# PatGen.net
KiCad netlist of a schematic drawn in EAGLE
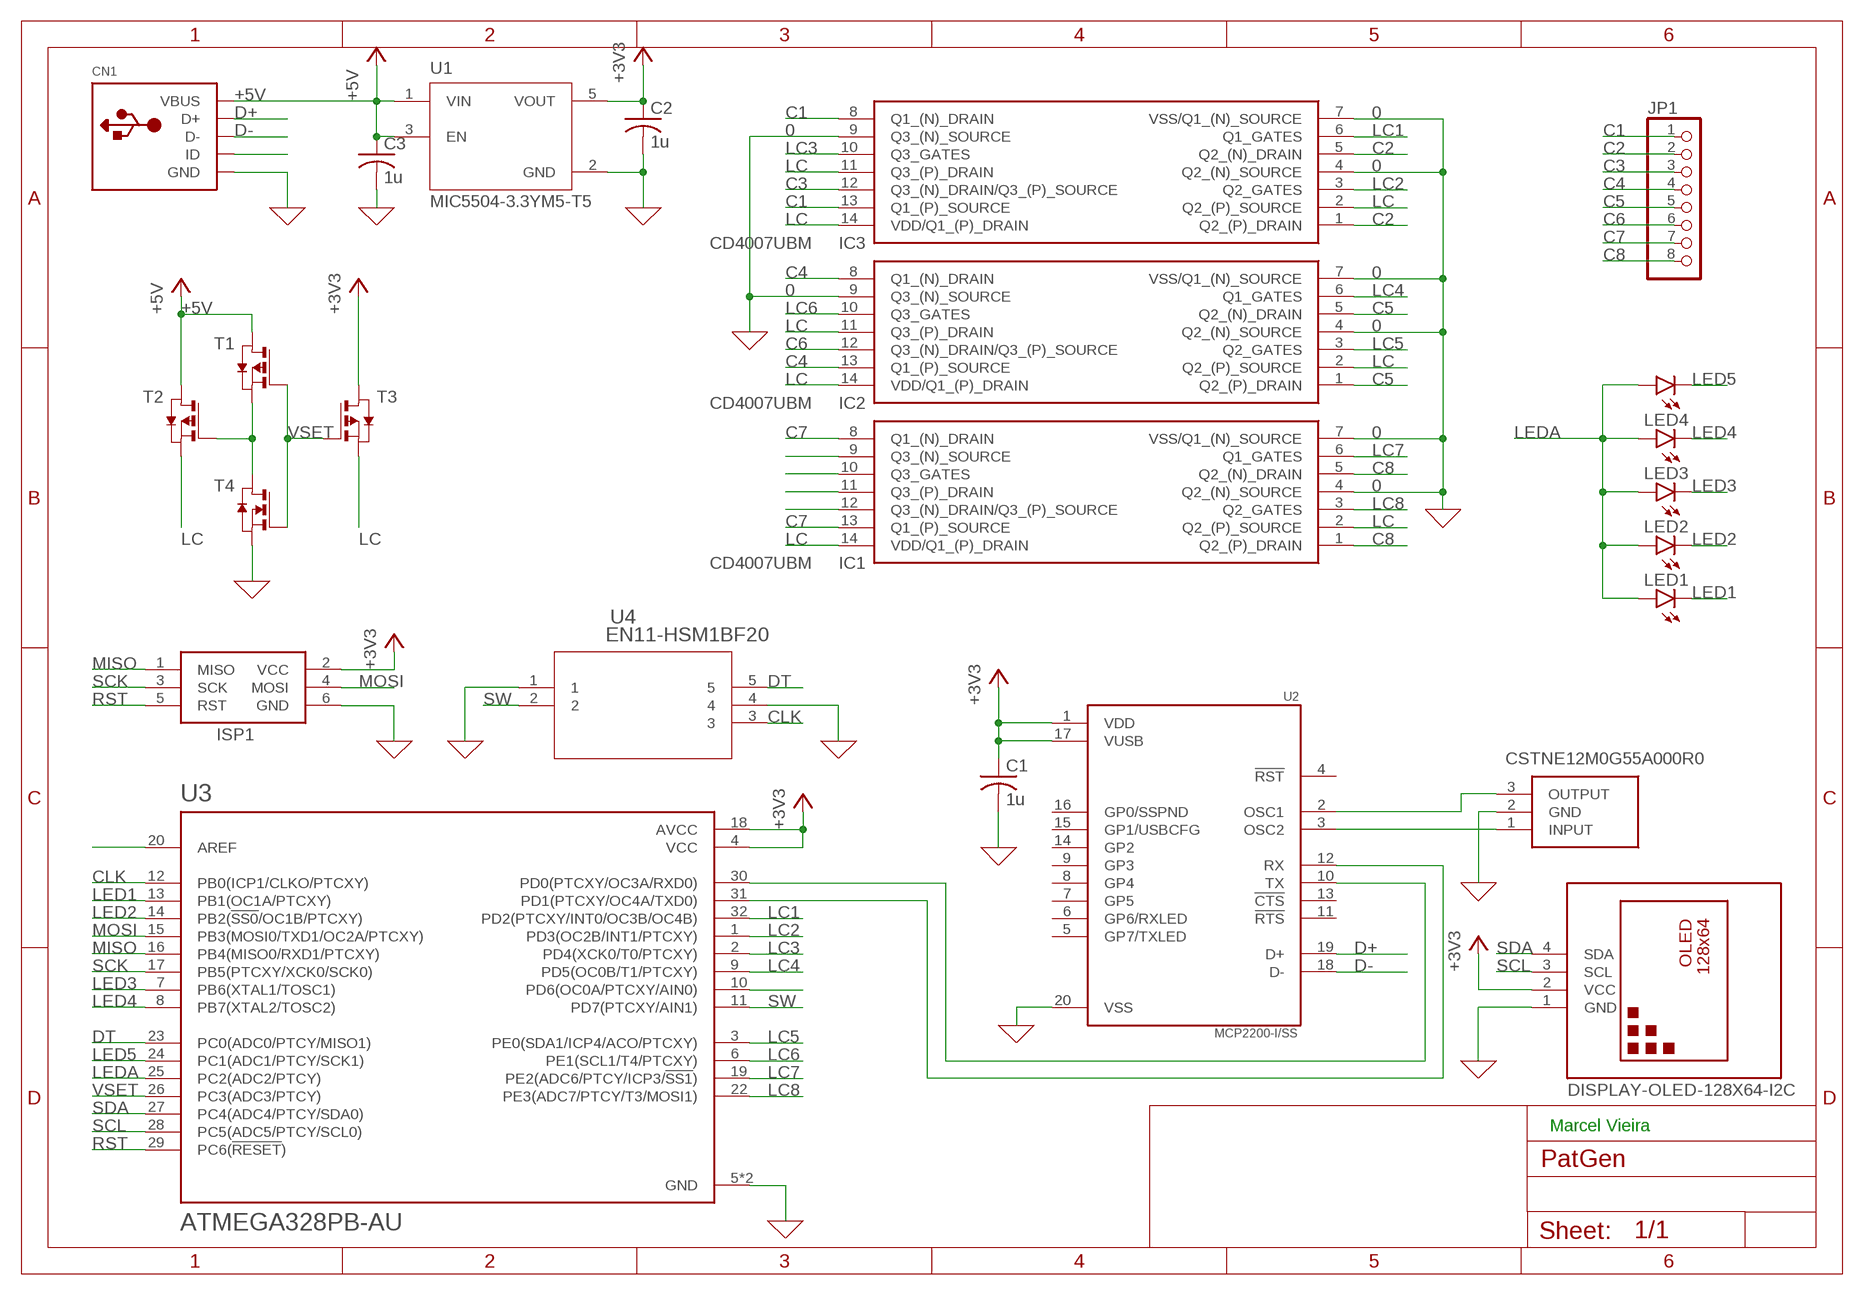
[diagram p0: schematic, sheet 1]

(export (version "E")
  (design (tool "Eeschema 10.0.6"))
  (components
    (comp (ref "C1")
      (value "1u")
      (footprint "eagle-import:C0805")
      (libsource (lib "eagle-import") (part "C-USC0805"))
    )
    (comp (ref "C2")
      (value "1u")
      (footprint "eagle-import:C0805")
      (libsource (lib "eagle-import") (part "C-USC0805"))
    )
    (comp (ref "C3")
      (value "1u")
      (footprint "eagle-import:C0805")
      (libsource (lib "eagle-import") (part "C-USC0805"))
    )
    (comp (ref "CN1")
      (value "USBMINIB")
      (footprint "eagle-import:USB-MINIB")
      (libsource (lib "eagle-import") (part "USBMINIB"))
    )
    (comp (ref "IC1")
      (value "CD4007UBM")
      (footprint "eagle-import:SOIC127P600X175-14N")
      (fields (field (name "MOUSER_PART_NUMBER") "595-CD4007UBM"))
      (libsource (lib "eagle-import") (part "CD4007UBM"))
    )
    (comp (ref "IC2")
      (value "CD4007UBM")
      (footprint "eagle-import:SOIC127P600X175-14N")
      (fields (field (name "MOUSER_PART_NUMBER") "595-CD4007UBM"))
      (libsource (lib "eagle-import") (part "CD4007UBM"))
    )
    (comp (ref "IC3")
      (value "CD4007UBM")
      (footprint "eagle-import:SOIC127P600X175-14N")
      (fields (field (name "MOUSER_PART_NUMBER") "595-CD4007UBM"))
      (libsource (lib "eagle-import") (part "CD4007UBM"))
    )
    (comp (ref "ISP1")
      (value "AVRISP-6")
      (footprint "eagle-import:AVRISP")
      (libsource (lib "eagle-import") (part "AVRISP-6"))
    )
    (comp (ref "JP1")
      (value "PINHD-1X8-3.5MM")
      (footprint "eagle-import:1X08-3.5MM")
      (libsource (lib "eagle-import") (part "PINHD-1X8-3.5MM"))
    )
    (comp (ref "LED1")
      (value "LEDCHIP-LED0805")
      (footprint "eagle-import:CHIP-LED0805")
      (libsource (lib "eagle-import") (part "LEDCHIP-LED0805"))
    )
    (comp (ref "LED2")
      (value "LEDCHIP-LED0805")
      (footprint "eagle-import:CHIP-LED0805")
      (libsource (lib "eagle-import") (part "LEDCHIP-LED0805"))
    )
    (comp (ref "LED3")
      (value "LEDCHIP-LED0805")
      (footprint "eagle-import:CHIP-LED0805")
      (libsource (lib "eagle-import") (part "LEDCHIP-LED0805"))
    )
    (comp (ref "LED4")
      (value "LEDCHIP-LED0805")
      (footprint "eagle-import:CHIP-LED0805")
      (libsource (lib "eagle-import") (part "LEDCHIP-LED0805"))
    )
    (comp (ref "LED5")
      (value "LEDCHIP-LED0805")
      (footprint "eagle-import:CHIP-LED0805")
      (libsource (lib "eagle-import") (part "LEDCHIP-LED0805"))
    )
    (comp (ref "T1")
      (value "PMOSSOT23")
      (footprint "eagle-import:SOT-23")
      (libsource (lib "eagle-import") (part "PMOSSOT23"))
    )
    (comp (ref "T2")
      (value "PMOSSOT23")
      (footprint "eagle-import:SOT-23")
      (libsource (lib "eagle-import") (part "PMOSSOT23"))
    )
    (comp (ref "T3")
      (value "PMOSSOT23")
      (footprint "eagle-import:SOT-23")
      (libsource (lib "eagle-import") (part "PMOSSOT23"))
    )
    (comp (ref "T4")
      (value "NMOSSOT23")
      (footprint "eagle-import:SOT-23")
      (libsource (lib "eagle-import") (part "NMOSSOT23"))
    )
    (comp (ref "U$1")
      (value "DISPLAY-OLED-128X64-I2C")
      (footprint "eagle-import:DISPLAY-OLED-128X64-I2C")
      (libsource (lib "eagle-import") (part "DISPLAY-OLED-128X64-I2C"))
    )
    (comp (ref "U1")
      (value "MIC5504-3.3YM5-T5")
      (footprint "eagle-import:SOT95P280X145-5N")
      (fields (field (name "MF") "Microchip"))
      (libsource (lib "eagle-import") (part "MIC5504-3.3YM5-T5"))
    )
    (comp (ref "U2")
      (value "MCP2200-I/SS")
      (footprint "eagle-import:SOP65P780X200-20N")
      (fields (field (name "MF") "Microchip"))
      (libsource (lib "eagle-import") (part "MCP2200-I/SS"))
    )
    (comp (ref "U3")
      (value "ATMEGA328PB-AU")
      (footprint "eagle-import:QFP80P900X900X120-32N")
      (fields (field (name "MF") "Microchip Technology / Atmel"))
      (libsource (lib "eagle-import") (part "ATMEGA328PB-AU"))
    )
    (comp (ref "U4")
      (value "EN11-HSM1BF20")
      (footprint "eagle-import:EN11-HSM_TTE")
      (libsource (lib "eagle-import") (part "EN11-HSM1BF20"))
    )
    (comp (ref "Y1")
      (value "CSTNE12M0G55A000R0")
      (footprint "eagle-import:CSTNE12M0G55A000R0")
      (fields (field (name "MOUSER_PART_NUMBER") "81-CSTNE12M0G55A000R"))
      (libsource (lib "eagle-import") (part "CSTNE12M0G55A000R0"))
    )
  )
  (nets
    (net (code "1") (name "+3V3") (class "Default")
      (node (ref "C1") (pin "1") (pinfunction "1_1") (pintype "passive"))
      (node (ref "C2") (pin "1") (pinfunction "1_1") (pintype "passive"))
      (node (ref "ISP1") (pin "2") (pinfunction "VCC_2") (pintype "power_in"))
      (node (ref "T3") (pin "1") (pinfunction "D_1") (pintype "passive"))
      (node (ref "U$1") (pin "2") (pinfunction "VCC_2") (pintype "power_in"))
      (node (ref "U1") (pin "5") (pinfunction "VOUT_5") (pintype "output"))
      (node (ref "U2") (pin "1") (pinfunction "VDD_1") (pintype "power_in"))
      (node (ref "U2") (pin "17") (pinfunction "VUSB_17") (pintype "power_in"))
      (node (ref "U3") (pin "18") (pinfunction "AVCC_18") (pintype "power_in"))
      (node (ref "U3") (pin "4") (pinfunction "VCC_4") (pintype "power_in"))
    )
    (net (code "2") (name "+5V") (class "Default")
      (node (ref "C3") (pin "1") (pinfunction "1_1") (pintype "passive"))
      (node (ref "CN1") (pin "VBUS") (pinfunction "VBUS_VBUS") (pintype "power_in"))
      (node (ref "T1") (pin "1") (pinfunction "D_1") (pintype "passive"))
      (node (ref "T2") (pin "1") (pinfunction "D_1") (pintype "passive"))
      (node (ref "U1") (pin "1") (pinfunction "VIN_1") (pintype "input"))
      (node (ref "U1") (pin "3") (pinfunction "EN_3") (pintype "input"))
    )
    (net (code "3") (name "/C1") (class "Default")
      (node (ref "IC3") (pin "13") (pinfunction "Q1_(P)_SOURCE_13") (pintype "bidirectional"))
      (node (ref "IC3") (pin "8") (pinfunction "Q1_(N)_DRAIN_8") (pintype "bidirectional"))
      (node (ref "JP1") (pin "1") (pinfunction "1_1") (pintype "passive"))
    )
    (net (code "4") (name "/C2") (class "Default")
      (node (ref "IC3") (pin "1") (pinfunction "Q2_(P)_DRAIN_1") (pintype "bidirectional"))
      (node (ref "IC3") (pin "5") (pinfunction "Q2_(N)_DRAIN_5") (pintype "bidirectional"))
      (node (ref "JP1") (pin "2") (pinfunction "2_2") (pintype "passive"))
    )
    (net (code "5") (name "/C3") (class "Default")
      (node (ref "IC3") (pin "12") (pinfunction "Q3_(N)_DRAIN/Q3_(P)_SOURCE_12") (pintype "bidirectional"))
      (node (ref "JP1") (pin "3") (pinfunction "3_3") (pintype "passive"))
    )
    (net (code "6") (name "/C4") (class "Default")
      (node (ref "IC2") (pin "13") (pinfunction "Q1_(P)_SOURCE_13") (pintype "bidirectional"))
      (node (ref "IC2") (pin "8") (pinfunction "Q1_(N)_DRAIN_8") (pintype "bidirectional"))
      (node (ref "JP1") (pin "4") (pinfunction "4_4") (pintype "passive"))
    )
    (net (code "7") (name "/C5") (class "Default")
      (node (ref "IC2") (pin "1") (pinfunction "Q2_(P)_DRAIN_1") (pintype "bidirectional"))
      (node (ref "IC2") (pin "5") (pinfunction "Q2_(N)_DRAIN_5") (pintype "bidirectional"))
      (node (ref "JP1") (pin "5") (pinfunction "5_5") (pintype "passive"))
    )
    (net (code "8") (name "/C6") (class "Default")
      (node (ref "IC2") (pin "12") (pinfunction "Q3_(N)_DRAIN/Q3_(P)_SOURCE_12") (pintype "bidirectional"))
      (node (ref "JP1") (pin "6") (pinfunction "6_6") (pintype "passive"))
    )
    (net (code "9") (name "/C7") (class "Default")
      (node (ref "IC1") (pin "13") (pinfunction "Q1_(P)_SOURCE_13") (pintype "bidirectional"))
      (node (ref "IC1") (pin "8") (pinfunction "Q1_(N)_DRAIN_8") (pintype "bidirectional"))
      (node (ref "JP1") (pin "7") (pinfunction "7_7") (pintype "passive"))
    )
    (net (code "10") (name "/C8") (class "Default")
      (node (ref "IC1") (pin "1") (pinfunction "Q2_(P)_DRAIN_1") (pintype "bidirectional"))
      (node (ref "IC1") (pin "5") (pinfunction "Q2_(N)_DRAIN_5") (pintype "bidirectional"))
      (node (ref "JP1") (pin "8") (pinfunction "8_8") (pintype "passive"))
    )
    (net (code "11") (name "/CLK") (class "Default")
      (node (ref "U3") (pin "12") (pinfunction "PB0(ICP1/CLKO/PTCXY)_12") (pintype "bidirectional"))
      (node (ref "U4") (pin "3") (pinfunction "3_3") (pintype "passive"))
    )
    (net (code "12") (name "/D+") (class "Default")
      (node (ref "CN1") (pin "D+") (pinfunction "D+_D+") (pintype "bidirectional"))
      (node (ref "U2") (pin "19") (pinfunction "D+_19") (pintype "bidirectional"))
    )
    (net (code "13") (name "/D-") (class "Default")
      (node (ref "CN1") (pin "D-") (pinfunction "D-_D-") (pintype "bidirectional"))
      (node (ref "U2") (pin "18") (pinfunction "D-_18") (pintype "bidirectional"))
    )
    (net (code "14") (name "/DT") (class "Default")
      (node (ref "U3") (pin "23") (pinfunction "PC0(ADC0/PTCY/MISO1)_23") (pintype "bidirectional"))
      (node (ref "U4") (pin "5") (pinfunction "5_5") (pintype "passive"))
    )
    (net (code "15") (name "/LC") (class "Default")
      (node (ref "IC1") (pin "14") (pinfunction "VDD/Q1_(P)_DRAIN_14") (pintype "bidirectional"))
      (node (ref "IC1") (pin "2") (pinfunction "Q2_(P)_SOURCE_2") (pintype "bidirectional"))
      (node (ref "IC2") (pin "11") (pinfunction "Q3_(P)_DRAIN_11") (pintype "bidirectional"))
      (node (ref "IC2") (pin "14") (pinfunction "VDD/Q1_(P)_DRAIN_14") (pintype "bidirectional"))
      (node (ref "IC2") (pin "2") (pinfunction "Q2_(P)_SOURCE_2") (pintype "bidirectional"))
      (node (ref "IC3") (pin "11") (pinfunction "Q3_(P)_DRAIN_11") (pintype "bidirectional"))
      (node (ref "IC3") (pin "14") (pinfunction "VDD/Q1_(P)_DRAIN_14") (pintype "bidirectional"))
      (node (ref "IC3") (pin "2") (pinfunction "Q2_(P)_SOURCE_2") (pintype "bidirectional"))
      (node (ref "T2") (pin "2") (pinfunction "S_2") (pintype "passive"))
      (node (ref "T3") (pin "2") (pinfunction "S_2") (pintype "passive"))
    )
    (net (code "16") (name "/LC1") (class "Default")
      (node (ref "IC3") (pin "6") (pinfunction "Q1_GATES_6") (pintype "bidirectional"))
      (node (ref "U3") (pin "32") (pinfunction "PD2(PTCXY/INT0/OC3B/OC4B)_32") (pintype "bidirectional"))
    )
    (net (code "17") (name "/LC2") (class "Default")
      (node (ref "IC3") (pin "3") (pinfunction "Q2_GATES_3") (pintype "bidirectional"))
      (node (ref "U3") (pin "1") (pinfunction "PD3(OC2B/INT1/PTCXY)_1") (pintype "bidirectional"))
    )
    (net (code "18") (name "/LC3") (class "Default")
      (node (ref "IC3") (pin "10") (pinfunction "Q3_GATES_10") (pintype "bidirectional"))
      (node (ref "U3") (pin "2") (pinfunction "PD4(XCK0/T0/PTCXY)_2") (pintype "bidirectional"))
    )
    (net (code "19") (name "/LC4") (class "Default")
      (node (ref "IC2") (pin "6") (pinfunction "Q1_GATES_6") (pintype "bidirectional"))
      (node (ref "U3") (pin "9") (pinfunction "PD5(OC0B/T1/PTCXY)_9") (pintype "bidirectional"))
    )
    (net (code "20") (name "/LC5") (class "Default")
      (node (ref "IC2") (pin "3") (pinfunction "Q2_GATES_3") (pintype "bidirectional"))
      (node (ref "U3") (pin "3") (pinfunction "PE0(SDA1/ICP4/ACO/PTCXY)_3") (pintype "bidirectional"))
    )
    (net (code "21") (name "/LC6") (class "Default")
      (node (ref "IC2") (pin "10") (pinfunction "Q3_GATES_10") (pintype "bidirectional"))
      (node (ref "U3") (pin "6") (pinfunction "PE1(SCL1/T4/PTCXY)_6") (pintype "bidirectional"))
    )
    (net (code "22") (name "/LC7") (class "Default")
      (node (ref "IC1") (pin "6") (pinfunction "Q1_GATES_6") (pintype "bidirectional"))
      (node (ref "U3") (pin "19") (pinfunction "PE2(ADC6/PTCY/ICP3/~{SS1})_19") (pintype "bidirectional"))
    )
    (net (code "23") (name "/LC8") (class "Default")
      (node (ref "IC1") (pin "3") (pinfunction "Q2_GATES_3") (pintype "bidirectional"))
      (node (ref "U3") (pin "22") (pinfunction "PE3(ADC7/PTCY/T3/MOSI1)_22") (pintype "bidirectional"))
    )
    (net (code "24") (name "/LED1") (class "Default")
      (node (ref "LED1") (pin "C") (pinfunction "C_C") (pintype "passive"))
      (node (ref "U3") (pin "13") (pinfunction "PB1(OC1A/PTCXY)_13") (pintype "bidirectional"))
    )
    (net (code "25") (name "/LED2") (class "Default")
      (node (ref "LED2") (pin "C") (pinfunction "C_C") (pintype "passive"))
      (node (ref "U3") (pin "14") (pinfunction "PB2(~{SS0}/OC1B/PTCXY)_14") (pintype "bidirectional"))
    )
    (net (code "26") (name "/LED3") (class "Default")
      (node (ref "LED3") (pin "C") (pinfunction "C_C") (pintype "passive"))
      (node (ref "U3") (pin "7") (pinfunction "PB6(XTAL1/TOSC1)_7") (pintype "bidirectional"))
    )
    (net (code "27") (name "/LED4") (class "Default")
      (node (ref "LED4") (pin "C") (pinfunction "C_C") (pintype "passive"))
      (node (ref "U3") (pin "8") (pinfunction "PB7(XTAL2/TOSC2)_8") (pintype "bidirectional"))
    )
    (net (code "28") (name "/LED5") (class "Default")
      (node (ref "LED5") (pin "C") (pinfunction "C_C") (pintype "passive"))
      (node (ref "U3") (pin "24") (pinfunction "PC1(ADC1/PTCY/SCK1)_24") (pintype "bidirectional"))
    )
    (net (code "29") (name "/LEDA") (class "Default")
      (node (ref "LED1") (pin "A") (pinfunction "A_A") (pintype "passive"))
      (node (ref "LED2") (pin "A") (pinfunction "A_A") (pintype "passive"))
      (node (ref "LED3") (pin "A") (pinfunction "A_A") (pintype "passive"))
      (node (ref "LED4") (pin "A") (pinfunction "A_A") (pintype "passive"))
      (node (ref "LED5") (pin "A") (pinfunction "A_A") (pintype "passive"))
      (node (ref "U3") (pin "25") (pinfunction "PC2(ADC2/PTCY)_25") (pintype "bidirectional"))
    )
    (net (code "30") (name "/MISO") (class "Default")
      (node (ref "ISP1") (pin "1") (pinfunction "MISO_1") (pintype "input"))
      (node (ref "U3") (pin "16") (pinfunction "PB4(MISO0/RXD1/PTCXY)_16") (pintype "bidirectional"))
    )
    (net (code "31") (name "/MOSI") (class "Default")
      (node (ref "ISP1") (pin "4") (pinfunction "MOSI_4") (pintype "output"))
      (node (ref "U3") (pin "15") (pinfunction "PB3(MOSI0/TXD1/OC2A/PTCXY)_15") (pintype "bidirectional"))
    )
    (net (code "32") (name "/RST") (class "Default")
      (node (ref "ISP1") (pin "5") (pinfunction "RST_5") (pintype "output"))
      (node (ref "U3") (pin "29") (pinfunction "PC6(~{RESET})_29") (pintype "bidirectional"))
    )
    (net (code "33") (name "/SCK") (class "Default")
      (node (ref "ISP1") (pin "3") (pinfunction "SCK_3") (pintype "output"))
      (node (ref "U3") (pin "17") (pinfunction "PB5(PTCXY/XCK0/SCK0)_17") (pintype "bidirectional"))
    )
    (net (code "34") (name "/SCL") (class "Default")
      (node (ref "U$1") (pin "3") (pinfunction "SCL_3") (pintype "bidirectional"))
      (node (ref "U3") (pin "28") (pinfunction "PC5(ADC5/PTCY/SCL0)_28") (pintype "bidirectional"))
    )
    (net (code "35") (name "/SDA") (class "Default")
      (node (ref "U$1") (pin "4") (pinfunction "SDA_4") (pintype "bidirectional"))
      (node (ref "U3") (pin "27") (pinfunction "PC4(ADC4/PTCY/SDA0)_27") (pintype "bidirectional"))
    )
    (net (code "36") (name "/SW") (class "Default")
      (node (ref "U3") (pin "11") (pinfunction "PD7(PTCXY/AIN1)_11") (pintype "bidirectional"))
      (node (ref "U4") (pin "2") (pinfunction "2_2") (pintype "passive"))
    )
    (net (code "37") (name "/VSET") (class "Default")
      (node (ref "T1") (pin "3") (pinfunction "G_3") (pintype "passive"))
      (node (ref "T3") (pin "3") (pinfunction "G_3") (pintype "passive"))
      (node (ref "T4") (pin "3") (pinfunction "G_3") (pintype "passive"))
      (node (ref "U3") (pin "26") (pinfunction "PC3(ADC3/PTCY)_26") (pintype "bidirectional"))
    )
    (net (code "38") (name "GND") (class "Default")
      (node (ref "C1") (pin "2") (pinfunction "2_2") (pintype "passive"))
      (node (ref "C2") (pin "2") (pinfunction "2_2") (pintype "passive"))
      (node (ref "C3") (pin "2") (pinfunction "2_2") (pintype "passive"))
      (node (ref "CN1") (pin "GND") (pinfunction "GND_GND") (pintype "power_in"))
      (node (ref "IC1") (pin "4") (pinfunction "Q2_(N)_SOURCE_4") (pintype "bidirectional"))
      (node (ref "IC1") (pin "7") (pinfunction "VSS/Q1_(N)_SOURCE_7") (pintype "bidirectional"))
      (node (ref "IC2") (pin "4") (pinfunction "Q2_(N)_SOURCE_4") (pintype "bidirectional"))
      (node (ref "IC2") (pin "7") (pinfunction "VSS/Q1_(N)_SOURCE_7") (pintype "bidirectional"))
      (node (ref "IC2") (pin "9") (pinfunction "Q3_(N)_SOURCE_9") (pintype "bidirectional"))
      (node (ref "IC3") (pin "4") (pinfunction "Q2_(N)_SOURCE_4") (pintype "bidirectional"))
      (node (ref "IC3") (pin "7") (pinfunction "VSS/Q1_(N)_SOURCE_7") (pintype "bidirectional"))
      (node (ref "IC3") (pin "9") (pinfunction "Q3_(N)_SOURCE_9") (pintype "bidirectional"))
      (node (ref "ISP1") (pin "6") (pinfunction "GND_6") (pintype "power_in"))
      (node (ref "T4") (pin "2") (pinfunction "S_2") (pintype "passive"))
      (node (ref "U$1") (pin "1") (pinfunction "GND_1") (pintype "power_in"))
      (node (ref "U1") (pin "2") (pinfunction "GND_2") (pintype "power_in"))
      (node (ref "U2") (pin "20") (pinfunction "VSS_20") (pintype "power_in"))
      (node (ref "U3") (pin "21") (pinfunction "GND_21") (pintype "power_in"))
      (node (ref "U3") (pin "5") (pinfunction "GND_5") (pintype "power_in"))
      (node (ref "U4") (pin "1") (pinfunction "1_1") (pintype "passive"))
      (node (ref "U4") (pin "4") (pinfunction "4_4") (pintype "passive"))
      (node (ref "Y1") (pin "2") (pinfunction "GND_2") (pintype "bidirectional"))
    )
    (net (code "39") (name "Net-(T1-S)") (class "Default")
      (node (ref "T1") (pin "2") (pinfunction "S_2") (pintype "passive"))
      (node (ref "T2") (pin "3") (pinfunction "G_3") (pintype "passive"))
      (node (ref "T4") (pin "1") (pinfunction "D_1") (pintype "passive"))
    )
    (net (code "40") (name "Net-(U2-OSC1)") (class "Default")
      (node (ref "U2") (pin "2") (pinfunction "OSC1_2") (pintype "input"))
      (node (ref "Y1") (pin "3") (pinfunction "OUTPUT_3") (pintype "bidirectional"))
    )
    (net (code "41") (name "Net-(U2-OSC2)") (class "Default")
      (node (ref "U2") (pin "3") (pinfunction "OSC2_3") (pintype "output"))
      (node (ref "Y1") (pin "1") (pinfunction "INPUT_1") (pintype "bidirectional"))
    )
    (net (code "42") (name "Net-(U2-RX)") (class "Default")
      (node (ref "U2") (pin "12") (pinfunction "RX_12") (pintype "input"))
      (node (ref "U3") (pin "31") (pinfunction "PD1(PTCXY/OC4A/TXD0)_31") (pintype "bidirectional"))
    )
    (net (code "43") (name "Net-(U2-TX)") (class "Default")
      (node (ref "U2") (pin "10") (pinfunction "TX_10") (pintype "output"))
      (node (ref "U3") (pin "30") (pinfunction "PD0(PTCXY/OC3A/RXD0)_30") (pintype "bidirectional"))
    )
    (net (code "44") (name "unconnected-(CN1-PadID)") (class "Default")
      (node (ref "CN1") (pin "ID") (pinfunction "ID_ID") (pintype "bidirectional"))
    )
    (net (code "45") (name "unconnected-(IC1-Q3_(N)_DRAIN{slash}Q3_(P)_SOURCE-Pad12)") (class "Default")
      (node (ref "IC1") (pin "12") (pinfunction "Q3_(N)_DRAIN/Q3_(P)_SOURCE_12") (pintype "bidirectional"))
    )
    (net (code "46") (name "unconnected-(IC1-Q3_(N)_SOURCE-Pad9)") (class "Default")
      (node (ref "IC1") (pin "9") (pinfunction "Q3_(N)_SOURCE_9") (pintype "bidirectional"))
    )
    (net (code "47") (name "unconnected-(IC1-Q3_(P)_DRAIN-Pad11)") (class "Default")
      (node (ref "IC1") (pin "11") (pinfunction "Q3_(P)_DRAIN_11") (pintype "bidirectional"))
    )
    (net (code "48") (name "unconnected-(IC1-Q3_GATES-Pad10)") (class "Default")
      (node (ref "IC1") (pin "10") (pinfunction "Q3_GATES_10") (pintype "bidirectional"))
    )
    (net (code "49") (name "unconnected-(U2-GP0{slash}SSPND-Pad16)") (class "Default")
      (node (ref "U2") (pin "16") (pinfunction "GP0/SSPND_16") (pintype "bidirectional"))
    )
    (net (code "50") (name "unconnected-(U2-GP1{slash}USBCFG-Pad15)") (class "Default")
      (node (ref "U2") (pin "15") (pinfunction "GP1/USBCFG_15") (pintype "bidirectional"))
    )
    (net (code "51") (name "unconnected-(U2-GP2-Pad14)") (class "Default")
      (node (ref "U2") (pin "14") (pinfunction "GP2_14") (pintype "bidirectional"))
    )
    (net (code "52") (name "unconnected-(U2-GP3-Pad9)") (class "Default")
      (node (ref "U2") (pin "9") (pinfunction "GP3_9") (pintype "bidirectional"))
    )
    (net (code "53") (name "unconnected-(U2-GP4-Pad8)") (class "Default")
      (node (ref "U2") (pin "8") (pinfunction "GP4_8") (pintype "bidirectional"))
    )
    (net (code "54") (name "unconnected-(U2-GP5-Pad7)") (class "Default")
      (node (ref "U2") (pin "7") (pinfunction "GP5_7") (pintype "bidirectional"))
    )
    (net (code "55") (name "unconnected-(U2-GP6{slash}RXLED-Pad6)") (class "Default")
      (node (ref "U2") (pin "6") (pinfunction "GP6/RXLED_6") (pintype "bidirectional"))
    )
    (net (code "56") (name "unconnected-(U2-GP7{slash}TXLED-Pad5)") (class "Default")
      (node (ref "U2") (pin "5") (pinfunction "GP7/TXLED_5") (pintype "bidirectional"))
    )
    (net (code "57") (name "unconnected-(U2-~{CTS}-Pad13)") (class "Default")
      (node (ref "U2") (pin "13") (pinfunction "~{CTS}_13") (pintype "input"))
    )
    (net (code "58") (name "unconnected-(U2-~{RST}-Pad4)") (class "Default")
      (node (ref "U2") (pin "4") (pinfunction "~{RST}_4") (pintype "input"))
    )
    (net (code "59") (name "unconnected-(U2-~{RTS}-Pad11)") (class "Default")
      (node (ref "U2") (pin "11") (pinfunction "~{RTS}_11") (pintype "output"))
    )
    (net (code "60") (name "unconnected-(U3-AREF-Pad20)") (class "Default")
      (node (ref "U3") (pin "20") (pinfunction "AREF_20") (pintype "input"))
    )
    (net (code "61") (name "unconnected-(U3-PD6(OC0A{slash}PTCXY{slash}AIN0)-Pad10)") (class "Default")
      (node (ref "U3") (pin "10") (pinfunction "PD6(OC0A/PTCXY/AIN0)_10") (pintype "bidirectional"))
    )
  )
)
